# Sheet2.net
KiCad netlist of a schematic drawn in Altium Designer
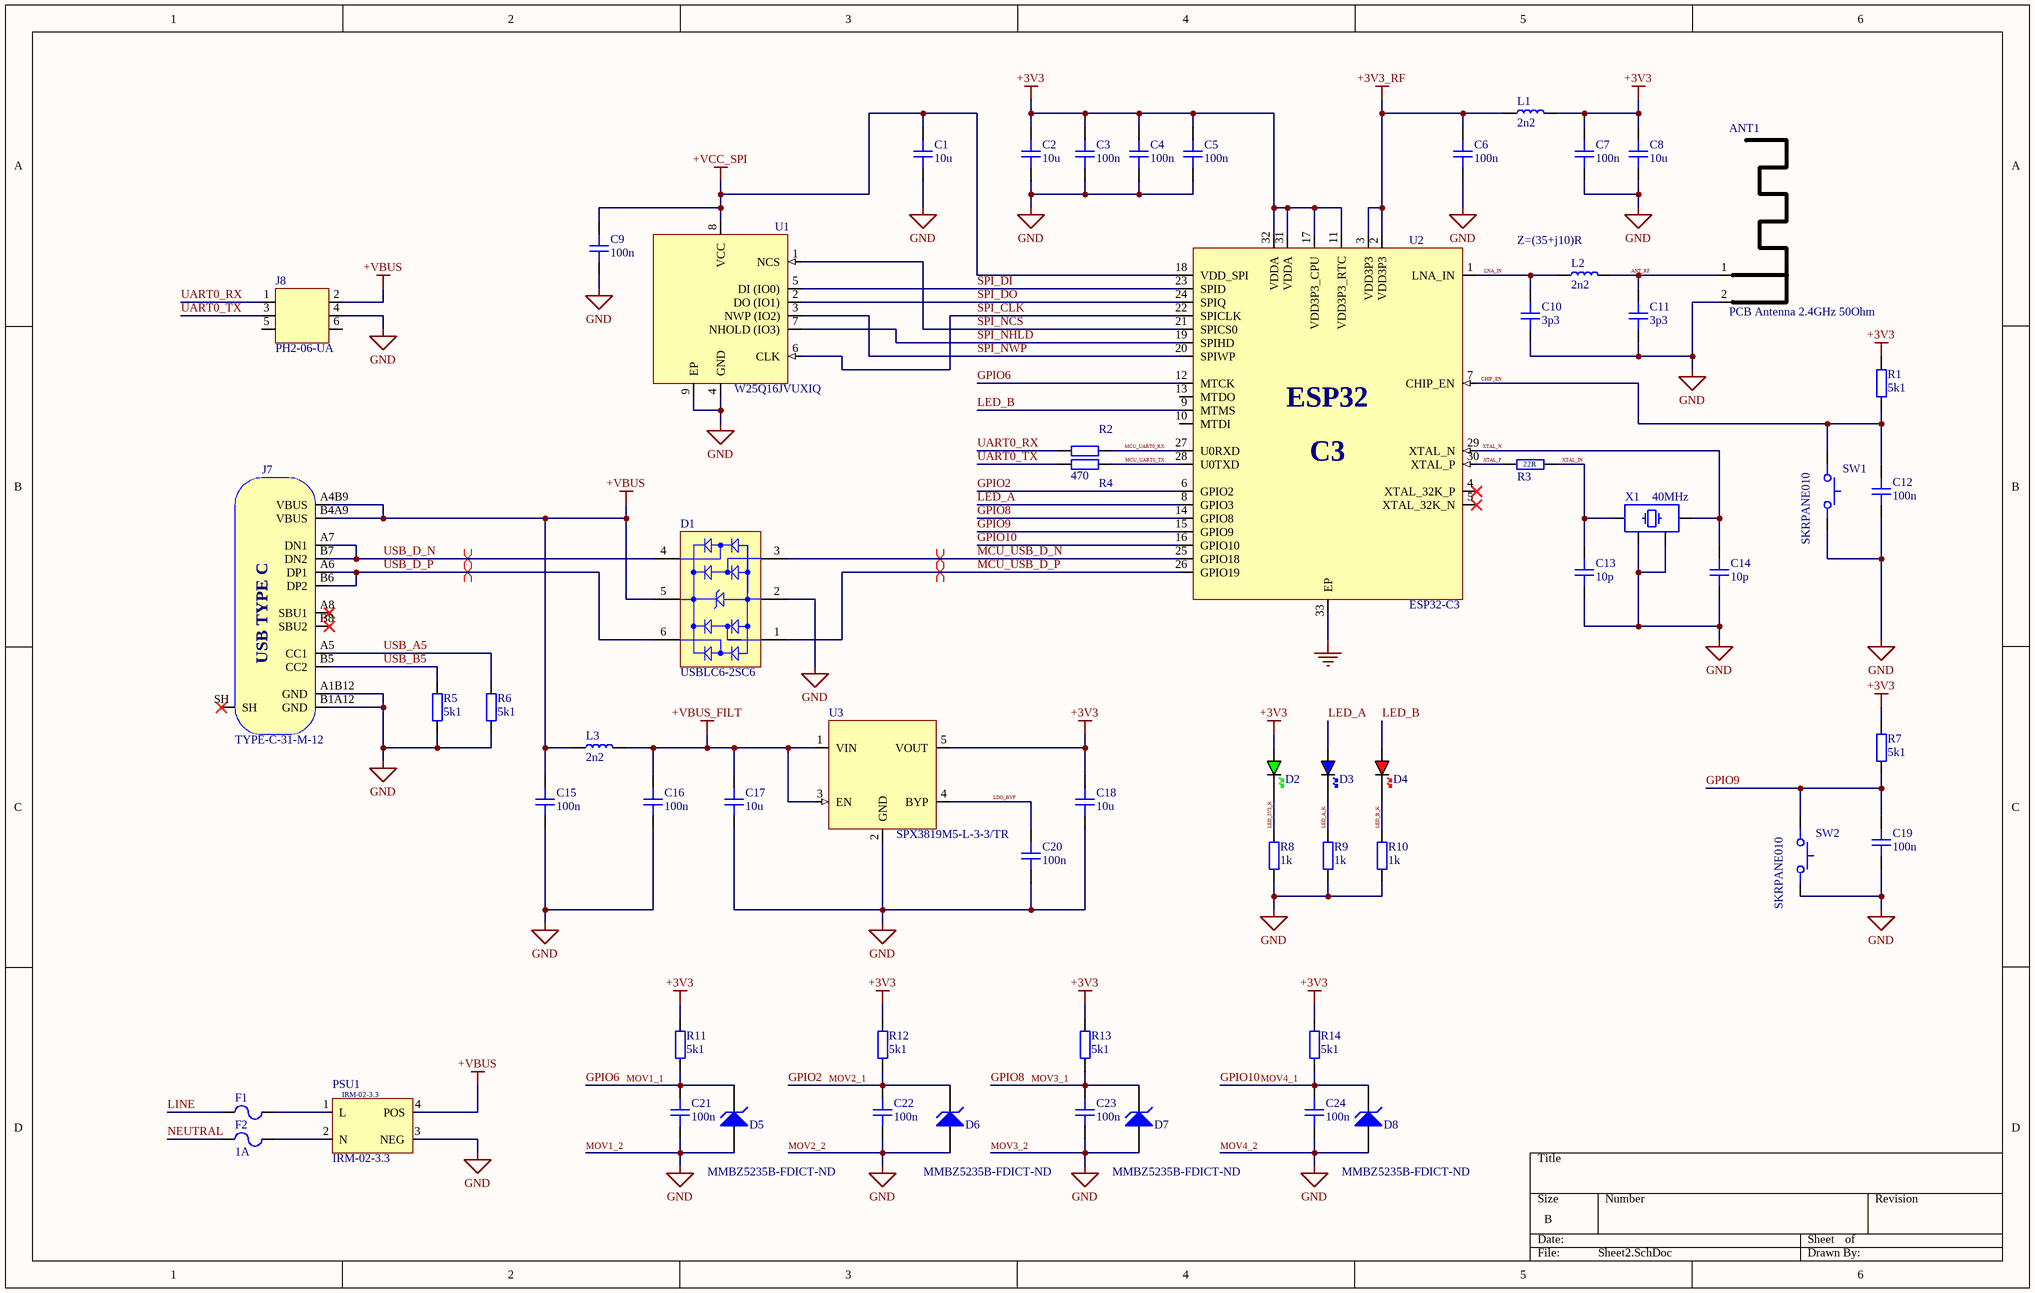
[diagram p0: Sheet2.SchDoc]

(export (version "E")
  (design (tool "Eeschema 10.0.6"))
  (components
    (comp (ref "ANT1")
      (value "PCB Antenna 2.4GHz 50Ohm")
      (footprint "ANT_IFA_USB_2_4GHZ_50R")
      (description "Inverted F 2.4GHz ISM PCB Antenna 50 Ohm")
      (libsource (lib "Schematic-Lib-PhilsLab") (part "ANT_IFA_USB_2_4GHZ_50R"))
    )
    (comp (ref "C1")
      (value "10u")
      (footprint "CAP_0603")
      (description "Capacitor SMD 0603 10V")
      (fields
        (field (name "MANUFACTURER") "Samsung")
        (field (name "MANUFACTURER PART NUMBER") "CL10A106KP8NNNC")
      )
      (libsource (lib "Schematic-Lib-PhilsLab") (part "CAP_0603_10V"))
    )
    (comp (ref "C2")
      (value "10u")
      (footprint "CAP_0603")
      (description "Capacitor SMD 0603 10V")
      (fields
        (field (name "MANUFACTURER") "Samsung")
        (field (name "MANUFACTURER PART NUMBER") "CL10A106KP8NNNC")
      )
      (libsource (lib "Schematic-Lib-PhilsLab") (part "CAP_0603_10V"))
    )
    (comp (ref "C3")
      (value "100n")
      (footprint "CAP_0805")
      (description "Capacitor SMD 0805 50V")
      (libsource (lib "Schematic-Lib-PhilsLab") (part "CAP_0805_50V"))
    )
    (comp (ref "C4")
      (value "100n")
      (footprint "CAP_0805")
      (description "Capacitor SMD 0805 50V")
      (libsource (lib "Schematic-Lib-PhilsLab") (part "CAP_0805_50V"))
    )
    (comp (ref "C5")
      (value "100n")
      (footprint "CAP_0805")
      (description "Capacitor SMD 0805 50V")
      (libsource (lib "Schematic-Lib-PhilsLab") (part "CAP_0805_50V"))
    )
    (comp (ref "C6")
      (value "100n")
      (footprint "CAP_0805")
      (description "Capacitor SMD 0805 50V")
      (libsource (lib "Schematic-Lib-PhilsLab") (part "CAP_0805_50V"))
    )
    (comp (ref "C7")
      (value "100n")
      (footprint "CAP_0805")
      (description "Capacitor SMD 0805 50V")
      (libsource (lib "Schematic-Lib-PhilsLab") (part "CAP_0805_50V"))
    )
    (comp (ref "C8")
      (value "10u")
      (footprint "CAP_0603")
      (description "Capacitor SMD 0603 10V")
      (fields
        (field (name "MANUFACTURER") "Samsung")
        (field (name "MANUFACTURER PART NUMBER") "CL10A106KP8NNNC")
      )
      (libsource (lib "Schematic-Lib-PhilsLab") (part "CAP_0603_10V"))
    )
    (comp (ref "C9")
      (value "100n")
      (footprint "CAP_0805")
      (description "Capacitor SMD 0805 50V")
      (libsource (lib "Schematic-Lib-PhilsLab") (part "CAP_0805_50V"))
    )
    (comp (ref "C10")
      (value "3p3")
      (footprint "CAP_0402")
      (description "Capacitor SMD 0402 50V")
      (fields (field (name "MANUFACTURER") "FH") (field (name "MANUFACTURER PART NUMBER") "0402CG3R3C500NT"))
      (libsource (lib "Schematic-Lib-PhilsLab") (part "CAP_0402_50V"))
    )
    (comp (ref "C11")
      (value "3p3")
      (footprint "CAP_0402")
      (description "Capacitor SMD 0402 50V")
      (fields (field (name "MANUFACTURER") "FH") (field (name "MANUFACTURER PART NUMBER") "0402CG3R3C500NT"))
      (libsource (lib "Schematic-Lib-PhilsLab") (part "CAP_0402_50V"))
    )
    (comp (ref "C12")
      (value "100n")
      (footprint "CAP_0805")
      (description "Capacitor SMD 0805 50V")
      (libsource (lib "Schematic-Lib-PhilsLab") (part "CAP_0805_50V"))
    )
    (comp (ref "C13")
      (value "10p")
      (footprint "CAP_0402")
      (description "Capacitor SMD 0402 50V")
      (fields
        (field (name "MANUFACTURER") "Samsung")
        (field (name "MANUFACTURER PART NUMBER") "CL05C100JB5NNNC")
      )
      (libsource (lib "Schematic-Lib-PhilsLab") (part "CAP_0402_50V"))
    )
    (comp (ref "C14")
      (value "10p")
      (footprint "CAP_0402")
      (description "Capacitor SMD 0402 50V")
      (fields
        (field (name "MANUFACTURER") "Samsung")
        (field (name "MANUFACTURER PART NUMBER") "CL05C100JB5NNNC")
      )
      (libsource (lib "Schematic-Lib-PhilsLab") (part "CAP_0402_50V"))
    )
    (comp (ref "C15")
      (value "100n")
      (footprint "CAP_0805")
      (description "Capacitor SMD 0805 50V")
      (libsource (lib "Schematic-Lib-PhilsLab") (part "CAP_0805_50V"))
    )
    (comp (ref "C16")
      (value "100n")
      (footprint "CAP_0805")
      (description "Capacitor SMD 0805 50V")
      (libsource (lib "Schematic-Lib-PhilsLab") (part "CAP_0805_50V"))
    )
    (comp (ref "C17")
      (value "10u")
      (footprint "CAP_0603")
      (description "Capacitor SMD 0603 10V")
      (fields
        (field (name "MANUFACTURER") "Samsung")
        (field (name "MANUFACTURER PART NUMBER") "CL10A106KP8NNNC")
      )
      (libsource (lib "Schematic-Lib-PhilsLab") (part "CAP_0603_10V"))
    )
    (comp (ref "C18")
      (value "10u")
      (footprint "CAP_0603")
      (description "Capacitor SMD 0603 10V")
      (fields
        (field (name "MANUFACTURER") "Samsung")
        (field (name "MANUFACTURER PART NUMBER") "CL10A106KP8NNNC")
      )
      (libsource (lib "Schematic-Lib-PhilsLab") (part "CAP_0603_10V"))
    )
    (comp (ref "C19")
      (value "100n")
      (footprint "CAP_0805")
      (description "Capacitor SMD 0805 50V")
      (libsource (lib "Schematic-Lib-PhilsLab") (part "CAP_0805_50V"))
    )
    (comp (ref "C20")
      (value "100n")
      (footprint "CAP_0805")
      (description "Capacitor SMD 0805 50V")
      (libsource (lib "Schematic-Lib-PhilsLab") (part "CAP_0805_50V"))
    )
    (comp (ref "C21")
      (value "100n")
      (footprint "CAP_0805")
      (description "Capacitor SMD 0805 50V")
      (libsource (lib "Schematic-Lib-PhilsLab") (part "CAP_0805_50V"))
    )
    (comp (ref "C22")
      (value "100n")
      (footprint "CAP_0805")
      (description "Capacitor SMD 0805 50V")
      (libsource (lib "Schematic-Lib-PhilsLab") (part "CAP_0805_50V"))
    )
    (comp (ref "C23")
      (value "100n")
      (footprint "CAP_0805")
      (description "Capacitor SMD 0805 50V")
      (libsource (lib "Schematic-Lib-PhilsLab") (part "CAP_0805_50V"))
    )
    (comp (ref "C24")
      (value "100n")
      (footprint "CAP_0805")
      (description "Capacitor SMD 0805 50V")
      (libsource (lib "Schematic-Lib-PhilsLab") (part "CAP_0805_50V"))
    )
    (comp (ref "D1")
      (value "USBLC6-2SC6")
      (footprint "STM-SOT23-6L_V")
      (description "Very low capacitance ESD protection, 3.5 pF, -40 to 125 degC, 6-Pin SOT23, RoHS, Tape and Reel")
      (fields (field (name "MANUFACTURER") "STMicroelectronics"))
      (libsource (lib "Altium Content Vault") (part "STM-USB_DVI_HDMIULC6-4SC6X-SOT23-6L"))
    )
    (comp (ref "D2")
      (value "GREEN")
      (footprint "LED_0603_GREEN")
      (description "LED 0603 GREEN SMD")
      (libsource (lib "Schematic-Lib-PhilsLab") (part "LED_0603_GREEN"))
    )
    (comp (ref "D3")
      (value "BLUE")
      (footprint "LED_0603_BLUE")
      (description "LED 0603 BLUE SMD")
      (libsource (lib "Schematic-Lib-PhilsLab") (part "LED_0603_BLUE"))
    )
    (comp (ref "D4")
      (value "RED")
      (footprint "LED_0603_RED")
      (description "LED 0603 RED SMD")
      (libsource (lib "Schematic-Lib-PhilsLab") (part "LED_0603_RED"))
    )
    (comp (ref "D5")
      (value "Diode, Zener, BZX84C18")
      (footprint "SOT23")
      (description "MMBZ5235B Series 350 mW 6.8 V 10 mA Surface Mount Zener Diode - SOT-23")
      (fields
        (field (name "MANUFACTURER") "Diodes")
        (field (name "TOLERANCE") "6%")
        (field (name "SUPPLIER PART NUMBER 2") "MMBZ5235B-FDICT-ND")
      )
      (libsource (lib "Erico_Ignitor") (part "Diode_BZX84C18"))
    )
    (comp (ref "D6")
      (value "Diode, Zener, BZX84C18")
      (footprint "SOT23")
      (description "MMBZ5235B Series 350 mW 6.8 V 10 mA Surface Mount Zener Diode - SOT-23")
      (fields
        (field (name "MANUFACTURER") "Diodes")
        (field (name "TOLERANCE") "6%")
        (field (name "SUPPLIER PART NUMBER 2") "MMBZ5235B-FDICT-ND")
      )
      (libsource (lib "Erico_Ignitor") (part "Diode_BZX84C18"))
    )
    (comp (ref "D7")
      (value "Diode, Zener, BZX84C18")
      (footprint "SOT23")
      (description "MMBZ5235B Series 350 mW 6.8 V 10 mA Surface Mount Zener Diode - SOT-23")
      (fields
        (field (name "MANUFACTURER") "Diodes")
        (field (name "TOLERANCE") "6%")
        (field (name "SUPPLIER PART NUMBER 2") "MMBZ5235B-FDICT-ND")
      )
      (libsource (lib "Erico_Ignitor") (part "Diode_BZX84C18"))
    )
    (comp (ref "D8")
      (value "Diode, Zener, BZX84C18")
      (footprint "SOT23")
      (description "MMBZ5235B Series 350 mW 6.8 V 10 mA Surface Mount Zener Diode - SOT-23")
      (fields
        (field (name "MANUFACTURER") "Diodes")
        (field (name "TOLERANCE") "6%")
        (field (name "SUPPLIER PART NUMBER 2") "MMBZ5235B-FDICT-ND")
      )
      (libsource (lib "Erico_Ignitor") (part "Diode_BZX84C18"))
    )
    (comp (ref "F1")
      (value "1A")
      (footprint "FUSE_6125N")
      (description "0422001.MR")
      (fields (field (name "MANUFACTURER") "Bel"))
      (libsource (lib "Erico_Ignitor") (part "FUSE_4A_SMT"))
    )
    (comp (ref "F2")
      (value "1A")
      (footprint "FUSE_6125N")
      (description "0422001.MR")
      (fields (field (name "MANUFACTURER") "Bel"))
      (libsource (lib "Erico_Ignitor") (part "FUSE_4A_SMT"))
    )
    (comp (ref "J7")
      (value "TYPE-C-31-M-12")
      (footprint "TYPE-C-31-M-12")
      (description "USB Type C Connector Horizontal SMT")
      (fields (field (name "MANUFACTURER") "Koren Hroparts"))
      (libsource (lib "Schematic-Lib-PhilsLab") (part "TYPE-C-31-M-12"))
    )
    (comp (ref "J8")
      (value "PH2-06-UA")
      (footprint "PH2-06-UA")
      (libsource (lib "SchLibrary") (part "PH2-06-UA"))
    )
    (comp (ref "L1")
      (value "2n2")
      (footprint "IND_0402")
      (description "Inductor SMD 0402")
      (fields
        (field (name "MANUFACTURER") "Murata")
        (field (name "MANUFACTURER PART NUMBER") "LQW15AN2N2G80D")
      )
      (libsource (lib "Schematic-Lib-PhilsLab") (part "IND_0402"))
    )
    (comp (ref "L2")
      (value "2n2")
      (footprint "IND_0402")
      (description "Inductor SMD 0402")
      (fields
        (field (name "MANUFACTURER") "Murata")
        (field (name "MANUFACTURER PART NUMBER") "LQW15AN2N2G80D")
      )
      (libsource (lib "Schematic-Lib-PhilsLab") (part "IND_0402"))
    )
    (comp (ref "L3")
      (value "2n2")
      (footprint "IND_0402")
      (description "Inductor SMD 0402")
      (fields
        (field (name "MANUFACTURER") "Murata")
        (field (name "MANUFACTURER PART NUMBER") "LQW15AN2N2G80D")
      )
      (libsource (lib "Schematic-Lib-PhilsLab") (part "IND_0402"))
    )
    (comp (ref "PSU1")
      (value "IRM-02-3.3")
      (footprint "IRM-02-3.3")
      (libsource (lib "SchLibrary") (part "IRM-02-3.3"))
    )
    (comp (ref "R1")
      (value "5k1")
      (footprint "RES_0805")
      (description "Resistor SMD 0805")
      (libsource (lib "Schematic-Lib-PhilsLab") (part "RES_0805"))
    )
    (comp (ref "R2")
      (value "470")
      (footprint "RES_0805")
      (description "Resistor SMD 0805")
      (libsource (lib "Schematic-Lib-PhilsLab") (part "RES_0805"))
    )
    (comp (ref "R3")
      (value "22R")
      (footprint "RES_0402")
      (description "Resistor SMD 0402")
      (fields
        (field (name "MANUFACTURER") "UNI-ROYAL")
        (field (name "MANUFACTURER PART NUMBER") "0402WGF220JTCE")
      )
      (libsource (lib "Schematic-Lib-PhilsLab") (part "RES_0402"))
    )
    (comp (ref "R4")
      (value "470")
      (footprint "RES_0805")
      (description "Resistor SMD 0805")
      (libsource (lib "Schematic-Lib-PhilsLab") (part "RES_0805"))
    )
    (comp (ref "R5")
      (value "5k1")
      (footprint "RES_0805")
      (description "Resistor SMD 0805")
      (libsource (lib "Schematic-Lib-PhilsLab") (part "RES_0805"))
    )
    (comp (ref "R6")
      (value "5k1")
      (footprint "RES_0805")
      (description "Resistor SMD 0805")
      (libsource (lib "Schematic-Lib-PhilsLab") (part "RES_0805"))
    )
    (comp (ref "R7")
      (value "5k1")
      (footprint "RES_0805")
      (description "Resistor SMD 0805")
      (libsource (lib "Schematic-Lib-PhilsLab") (part "RES_0805"))
    )
    (comp (ref "R8")
      (value "1k")
      (footprint "RES_0805")
      (description "Resistor SMD 0805")
      (libsource (lib "Schematic-Lib-PhilsLab") (part "RES_0805"))
    )
    (comp (ref "R9")
      (value "1k")
      (footprint "RES_0805")
      (description "Resistor SMD 0805")
      (libsource (lib "Schematic-Lib-PhilsLab") (part "RES_0805"))
    )
    (comp (ref "R10")
      (value "1k")
      (footprint "RES_0805")
      (description "Resistor SMD 0805")
      (libsource (lib "Schematic-Lib-PhilsLab") (part "RES_0805"))
    )
    (comp (ref "R11")
      (value "5k1")
      (footprint "RES_0805")
      (description "Resistor SMD 0805")
      (libsource (lib "Schematic-Lib-PhilsLab") (part "RES_0805"))
    )
    (comp (ref "R12")
      (value "5k1")
      (footprint "RES_0805")
      (description "Resistor SMD 0805")
      (libsource (lib "Schematic-Lib-PhilsLab") (part "RES_0805"))
    )
    (comp (ref "R13")
      (value "5k1")
      (footprint "RES_0805")
      (description "Resistor SMD 0805")
      (libsource (lib "Schematic-Lib-PhilsLab") (part "RES_0805"))
    )
    (comp (ref "R14")
      (value "5k1")
      (footprint "RES_0805")
      (description "Resistor SMD 0805")
      (libsource (lib "Schematic-Lib-PhilsLab") (part "RES_0805"))
    )
    (comp (ref "SW1")
      (value "SKRPANE010")
      (footprint "SKRPANE010")
      (description "Tactile Switch SMD SPST")
      (fields (field (name "MANUFACTURER") "Alps Alpine"))
      (libsource (lib "Schematic-Lib-PhilsLab") (part "SKRPANE010"))
    )
    (comp (ref "SW2")
      (value "SKRPANE010")
      (footprint "SKRPANE010")
      (description "Tactile Switch SMD SPST")
      (fields (field (name "MANUFACTURER") "Alps Alpine"))
      (libsource (lib "Schematic-Lib-PhilsLab") (part "SKRPANE010"))
    )
    (comp (ref "U1")
      (value "W25Q16JVUXIQ")
      (footprint "USON-8-2X3MM")
      (description "16M-BIT SERIAL FLASH MEMORY WITH\r\nDUAL/QUAD SPI USON-8")
      (fields (field (name "MANUFACTURER") "Winbond"))
      (libsource (lib "Schematic-Lib-PhilsLab") (part "W25Q16JVUXIQ"))
    )
    (comp (ref "U2")
      (value "ESP32-C3")
      (footprint "QFN32-5x5")
      (fields (field (name "MANUFACTURER") "Espressif"))
      (libsource (lib "Schematic-Lib-PhilsLab") (part "ESP32-C3"))
    )
    (comp (ref "U3")
      (value "SPX3819M5-L-3-3/TR")
      (footprint "SOT-23-5")
      (description "500mA +3.3V Low-Noise LDO Voltage Regulator")
      (fields (field (name "MANUFACTURER") "MaxLinear"))
      (libsource (lib "Schematic-Lib-PhilsLab") (part "SPX3819M5-L-3-3/TR"))
    )
    (comp (ref "X1")
      (value "40MHz")
      (footprint "XTAL_2520")
      (description "Crystal SMD 2520")
      (fields (field (name "MANUFACTURER") "Seiko Epson"))
      (libsource (lib "Schematic-Lib-PhilsLab") (part "XTAL_2520"))
    )
  )
  (nets
    (net (code "1") (name "+3V3") (class "Default")
      (node (ref "C18") (pin "2") (pinfunction "2_2") (pintype "passive"))
      (node (ref "C2") (pin "2") (pinfunction "2_2") (pintype "passive"))
      (node (ref "C3") (pin "2") (pinfunction "2_2") (pintype "passive"))
      (node (ref "C4") (pin "2") (pinfunction "2_2") (pintype "passive"))
      (node (ref "C5") (pin "2") (pinfunction "2_2") (pintype "passive"))
      (node (ref "C7") (pin "2") (pinfunction "2_2") (pintype "passive"))
      (node (ref "C8") (pin "2") (pinfunction "2_2") (pintype "passive"))
      (node (ref "D2") (pin "A") (pinfunction "A_A") (pintype "passive"))
      (node (ref "L1") (pin "1") (pinfunction "1_1") (pintype "passive"))
      (node (ref "R1") (pin "2") (pinfunction "2_2") (pintype "passive"))
      (node (ref "R11") (pin "2") (pinfunction "2_2") (pintype "passive"))
      (node (ref "R12") (pin "2") (pinfunction "2_2") (pintype "passive"))
      (node (ref "R13") (pin "2") (pinfunction "2_2") (pintype "passive"))
      (node (ref "R14") (pin "2") (pinfunction "2_2") (pintype "passive"))
      (node (ref "R7") (pin "2") (pinfunction "2_2") (pintype "passive"))
      (node (ref "U2") (pin "11") (pinfunction "VDD3P3_RTC_11") (pintype "power_in"))
      (node (ref "U2") (pin "17") (pinfunction "VDD3P3_CPU_17") (pintype "power_in"))
      (node (ref "U2") (pin "31") (pinfunction "VDDA_31") (pintype "power_in"))
      (node (ref "U2") (pin "32") (pinfunction "VDDA_32") (pintype "power_in"))
      (node (ref "U3") (pin "5") (pinfunction "VOUT_5") (pintype "power_in"))
    )
    (net (code "2") (name "+3V3_RF") (class "Default")
      (node (ref "C6") (pin "2") (pinfunction "2_2") (pintype "passive"))
      (node (ref "L1") (pin "2") (pinfunction "2_2") (pintype "passive"))
      (node (ref "U2") (pin "2") (pinfunction "VDD3P3_2") (pintype "power_in"))
      (node (ref "U2") (pin "3") (pinfunction "VDD3P3_3") (pintype "power_in"))
    )
    (net (code "3") (name "+VBUS") (class "Default")
      (node (ref "C15") (pin "2") (pinfunction "2_2") (pintype "passive"))
      (node (ref "D1") (pin "5") (pinfunction "VBUS_5") (pintype "passive"))
      (node (ref "J7") (pin "A4B9") (pinfunction "VBUS_A4B9") (pintype "power_in"))
      (node (ref "J7") (pin "B4A9") (pinfunction "VBUS_B4A9") (pintype "power_in"))
      (node (ref "J8") (pin "2") (pinfunction "2_2") (pintype "passive"))
      (node (ref "L3") (pin "2") (pinfunction "2_2") (pintype "passive"))
      (node (ref "PSU1") (pin "4") (pinfunction "POS_4") (pintype "passive"))
    )
    (net (code "4") (name "+VBUS_FILT") (class "Default")
      (node (ref "C16") (pin "2") (pinfunction "2_2") (pintype "passive"))
      (node (ref "C17") (pin "2") (pinfunction "2_2") (pintype "passive"))
      (node (ref "L3") (pin "1") (pinfunction "1_1") (pintype "passive"))
      (node (ref "U3") (pin "1") (pinfunction "VIN_1") (pintype "power_in"))
      (node (ref "U3") (pin "3") (pinfunction "EN_3") (pintype "input"))
    )
    (net (code "5") (name "+VCC_SPI") (class "Default")
      (node (ref "C1") (pin "2") (pinfunction "2_2") (pintype "passive"))
      (node (ref "C9") (pin "2") (pinfunction "2_2") (pintype "passive"))
      (node (ref "U1") (pin "8") (pinfunction "VCC_8") (pintype "power_in"))
      (node (ref "U2") (pin "18") (pinfunction "VDD_SPI_18") (pintype "power_in"))
    )
    (net (code "6") (name "/ANT_RF") (class "Default")
      (node (ref "ANT1") (pin "1") (pinfunction "RF_1") (pintype "passive"))
      (node (ref "C11") (pin "2") (pinfunction "2_2") (pintype "passive"))
      (node (ref "L2") (pin "1") (pinfunction "1_1") (pintype "passive"))
    )
    (net (code "7") (name "/CHIP_EN") (class "Default")
      (node (ref "C12") (pin "2") (pinfunction "2_2") (pintype "passive"))
      (node (ref "R1") (pin "1") (pinfunction "1_1") (pintype "passive"))
      (node (ref "SW1") (pin "34") (pintype "passive"))
      (node (ref "U2") (pin "7") (pinfunction "CHIP_EN_7") (pintype "input"))
    )
    (net (code "8") (name "/GPIO2") (class "Default")
      (node (ref "C22") (pin "2") (pinfunction "2_2") (pintype "passive"))
      (node (ref "D6") (pin "3") (pinfunction "K_3") (pintype "passive"))
      (node (ref "R12") (pin "1") (pinfunction "1_1") (pintype "passive"))
      (node (ref "U2") (pin "6") (pinfunction "GPIO2_6") (pintype "bidirectional"))
    )
    (net (code "9") (name "/GPIO6") (class "Default")
      (node (ref "C21") (pin "2") (pinfunction "2_2") (pintype "passive"))
      (node (ref "D5") (pin "3") (pinfunction "K_3") (pintype "passive"))
      (node (ref "R11") (pin "1") (pinfunction "1_1") (pintype "passive"))
      (node (ref "U2") (pin "12") (pinfunction "MTCK_12") (pintype "bidirectional"))
    )
    (net (code "10") (name "/GPIO8") (class "Default")
      (node (ref "C23") (pin "2") (pinfunction "2_2") (pintype "passive"))
      (node (ref "D7") (pin "3") (pinfunction "K_3") (pintype "passive"))
      (node (ref "R13") (pin "1") (pinfunction "1_1") (pintype "passive"))
      (node (ref "U2") (pin "14") (pinfunction "GPIO8_14") (pintype "bidirectional"))
    )
    (net (code "11") (name "/GPIO9") (class "Default")
      (node (ref "C19") (pin "2") (pinfunction "2_2") (pintype "passive"))
      (node (ref "R7") (pin "1") (pinfunction "1_1") (pintype "passive"))
      (node (ref "SW2") (pin "34") (pintype "passive"))
      (node (ref "U2") (pin "15") (pinfunction "GPIO9_15") (pintype "bidirectional"))
    )
    (net (code "12") (name "/GPIO10") (class "Default")
      (node (ref "C24") (pin "2") (pinfunction "2_2") (pintype "passive"))
      (node (ref "D8") (pin "3") (pinfunction "K_3") (pintype "passive"))
      (node (ref "R14") (pin "1") (pinfunction "1_1") (pintype "passive"))
      (node (ref "U2") (pin "16") (pinfunction "GPIO10_16") (pintype "bidirectional"))
    )
    (net (code "13") (name "/LDO_BYP") (class "Default")
      (node (ref "C20") (pin "2") (pinfunction "2_2") (pintype "passive"))
      (node (ref "U3") (pin "4") (pinfunction "BYP_4") (pintype "passive"))
    )
    (net (code "14") (name "/LED_3V3_K") (class "Default")
      (node (ref "D2") (pin "K") (pinfunction "K_K") (pintype "passive"))
      (node (ref "R8") (pin "2") (pinfunction "2_2") (pintype "passive"))
    )
    (net (code "15") (name "/LED_A") (class "Default")
      (node (ref "D3") (pin "A") (pinfunction "A_A") (pintype "passive"))
      (node (ref "U2") (pin "8") (pinfunction "GPIO3_8") (pintype "bidirectional"))
    )
    (net (code "16") (name "/LED_A_K") (class "Default")
      (node (ref "D3") (pin "K") (pinfunction "K_K") (pintype "passive"))
      (node (ref "R9") (pin "2") (pinfunction "2_2") (pintype "passive"))
    )
    (net (code "17") (name "/LED_B") (class "Default")
      (node (ref "D4") (pin "A") (pinfunction "A_A") (pintype "passive"))
      (node (ref "U2") (pin "9") (pinfunction "MTMS_9") (pintype "bidirectional"))
    )
    (net (code "18") (name "/LED_B_K") (class "Default")
      (node (ref "D4") (pin "K") (pinfunction "K_K") (pintype "passive"))
      (node (ref "R10") (pin "2") (pinfunction "2_2") (pintype "passive"))
    )
    (net (code "19") (name "/LINE") (class "Default")
      (node (ref "F1") (pin "1") (pinfunction "1_1") (pintype "passive"))
    )
    (net (code "20") (name "/LNA_IN") (class "Default")
      (node (ref "C10") (pin "2") (pinfunction "2_2") (pintype "passive"))
      (node (ref "L2") (pin "2") (pinfunction "2_2") (pintype "passive"))
      (node (ref "U2") (pin "1") (pinfunction "LNA_IN_1") (pintype "bidirectional"))
    )
    (net (code "21") (name "/MCU_UART0_RX") (class "Default")
      (node (ref "R2") (pin "1") (pinfunction "1_1") (pintype "passive"))
      (node (ref "U2") (pin "27") (pinfunction "U0RXD_27") (pintype "bidirectional"))
    )
    (net (code "22") (name "/MCU_UART0_TX") (class "Default")
      (node (ref "R4") (pin "1") (pinfunction "1_1") (pintype "passive"))
      (node (ref "U2") (pin "28") (pinfunction "U0TXD_28") (pintype "bidirectional"))
    )
    (net (code "23") (name "/MCU_USB_D_N") (class "Default")
      (node (ref "D1") (pin "3") (pinfunction "I/O_2_3") (pintype "passive"))
      (node (ref "U2") (pin "25") (pinfunction "GPIO18_25") (pintype "bidirectional"))
    )
    (net (code "24") (name "/MCU_USB_D_P") (class "Default")
      (node (ref "D1") (pin "1") (pinfunction "I/O_1_1") (pintype "passive"))
      (node (ref "U2") (pin "26") (pinfunction "GPIO19_26") (pintype "bidirectional"))
    )
    (net (code "25") (name "/NEUTRAL") (class "Default")
      (node (ref "F2") (pin "1") (pinfunction "1_1") (pintype "passive"))
    )
    (net (code "26") (name "/SPI_CLK") (class "Default")
      (node (ref "U1") (pin "6") (pinfunction "CLK_6") (pintype "input"))
      (node (ref "U2") (pin "22") (pinfunction "SPICLK_22") (pintype "bidirectional"))
    )
    (net (code "27") (name "/SPI_DI") (class "Default")
      (node (ref "U1") (pin "5") (pinfunction "DI_(IO0)_5") (pintype "bidirectional"))
      (node (ref "U2") (pin "23") (pinfunction "SPID_23") (pintype "bidirectional"))
    )
    (net (code "28") (name "/SPI_DO") (class "Default")
      (node (ref "U1") (pin "2") (pinfunction "DO_(IO1)_2") (pintype "bidirectional"))
      (node (ref "U2") (pin "24") (pinfunction "SPIQ_24") (pintype "bidirectional"))
    )
    (net (code "29") (name "/SPI_NCS") (class "Default")
      (node (ref "U1") (pin "1") (pinfunction "NCS_1") (pintype "input"))
      (node (ref "U2") (pin "21") (pinfunction "SPICS0_21") (pintype "bidirectional"))
    )
    (net (code "30") (name "/SPI_NHLD") (class "Default")
      (node (ref "U1") (pin "7") (pinfunction "NHOLD_(IO3)_7") (pintype "bidirectional"))
      (node (ref "U2") (pin "19") (pinfunction "SPIHD_19") (pintype "bidirectional"))
    )
    (net (code "31") (name "/SPI_NWP") (class "Default")
      (node (ref "U1") (pin "3") (pinfunction "NWP_(IO2)_3") (pintype "bidirectional"))
      (node (ref "U2") (pin "20") (pinfunction "SPIWP_20") (pintype "bidirectional"))
    )
    (net (code "32") (name "/UART0_RX") (class "Default")
      (node (ref "J8") (pin "1") (pinfunction "1_1") (pintype "passive"))
      (node (ref "R2") (pin "2") (pinfunction "2_2") (pintype "passive"))
    )
    (net (code "33") (name "/UART0_TX") (class "Default")
      (node (ref "J8") (pin "3") (pinfunction "3_3") (pintype "passive"))
      (node (ref "R4") (pin "2") (pinfunction "2_2") (pintype "passive"))
    )
    (net (code "34") (name "/USB_A5") (class "Default")
      (node (ref "J7") (pin "A5") (pinfunction "CC1_A5") (pintype "passive"))
      (node (ref "R6") (pin "2") (pinfunction "2_2") (pintype "passive"))
    )
    (net (code "35") (name "/USB_B5") (class "Default")
      (node (ref "J7") (pin "B5") (pinfunction "CC2_B5") (pintype "tri_state"))
      (node (ref "R5") (pin "2") (pinfunction "2_2") (pintype "passive"))
    )
    (net (code "36") (name "/USB_D_N") (class "Default")
      (node (ref "D1") (pin "4") (pinfunction "I/O_3_4") (pintype "passive"))
      (node (ref "J7") (pin "A7") (pinfunction "DN1_A7") (pintype "bidirectional"))
      (node (ref "J7") (pin "B7") (pinfunction "DN2_B7") (pintype "bidirectional"))
    )
    (net (code "37") (name "/USB_D_P") (class "Default")
      (node (ref "D1") (pin "6") (pinfunction "I/O_4_6") (pintype "passive"))
      (node (ref "J7") (pin "A6") (pinfunction "DP1_A6") (pintype "bidirectional"))
      (node (ref "J7") (pin "B6") (pinfunction "DP2_B6") (pintype "bidirectional"))
    )
    (net (code "38") (name "/XTAL_IN") (class "Default")
      (node (ref "C13") (pin "2") (pinfunction "2_2") (pintype "passive"))
      (node (ref "R3") (pin "2") (pinfunction "2_2") (pintype "passive"))
      (node (ref "X1") (pin "3") (pinfunction "3_3") (pintype "passive"))
    )
    (net (code "39") (name "/XTAL_N") (class "Default")
      (node (ref "C14") (pin "2") (pinfunction "2_2") (pintype "passive"))
      (node (ref "U2") (pin "29") (pinfunction "XTAL_N_29") (pintype "input"))
      (node (ref "X1") (pin "1") (pinfunction "1_1") (pintype "passive"))
    )
    (net (code "40") (name "/XTAL_P") (class "Default")
      (node (ref "R3") (pin "1") (pinfunction "1_1") (pintype "passive"))
      (node (ref "U2") (pin "30") (pinfunction "XTAL_P_30") (pintype "input"))
    )
    (net (code "41") (name "GND") (class "Default")
      (node (ref "ANT1") (pin "2") (pinfunction "GND_2") (pintype "passive"))
      (node (ref "C1") (pin "1") (pinfunction "1_1") (pintype "passive"))
      (node (ref "C10") (pin "1") (pinfunction "1_1") (pintype "passive"))
      (node (ref "C11") (pin "1") (pinfunction "1_1") (pintype "passive"))
      (node (ref "C12") (pin "1") (pinfunction "1_1") (pintype "passive"))
      (node (ref "C13") (pin "1") (pinfunction "1_1") (pintype "passive"))
      (node (ref "C14") (pin "1") (pinfunction "1_1") (pintype "passive"))
      (node (ref "C15") (pin "1") (pinfunction "1_1") (pintype "passive"))
      (node (ref "C16") (pin "1") (pinfunction "1_1") (pintype "passive"))
      (node (ref "C17") (pin "1") (pinfunction "1_1") (pintype "passive"))
      (node (ref "C18") (pin "1") (pinfunction "1_1") (pintype "passive"))
      (node (ref "C19") (pin "1") (pinfunction "1_1") (pintype "passive"))
      (node (ref "C2") (pin "1") (pinfunction "1_1") (pintype "passive"))
      (node (ref "C20") (pin "1") (pinfunction "1_1") (pintype "passive"))
      (node (ref "C21") (pin "1") (pinfunction "1_1") (pintype "passive"))
      (node (ref "C22") (pin "1") (pinfunction "1_1") (pintype "passive"))
      (node (ref "C23") (pin "1") (pinfunction "1_1") (pintype "passive"))
      (node (ref "C24") (pin "1") (pinfunction "1_1") (pintype "passive"))
      (node (ref "C3") (pin "1") (pinfunction "1_1") (pintype "passive"))
      (node (ref "C4") (pin "1") (pinfunction "1_1") (pintype "passive"))
      (node (ref "C5") (pin "1") (pinfunction "1_1") (pintype "passive"))
      (node (ref "C6") (pin "1") (pinfunction "1_1") (pintype "passive"))
      (node (ref "C7") (pin "1") (pinfunction "1_1") (pintype "passive"))
      (node (ref "C8") (pin "1") (pinfunction "1_1") (pintype "passive"))
      (node (ref "C9") (pin "1") (pinfunction "1_1") (pintype "passive"))
      (node (ref "D1") (pin "2") (pinfunction "GND_2") (pintype "passive"))
      (node (ref "D5") (pin "1") (pinfunction "A_1") (pintype "passive"))
      (node (ref "D6") (pin "1") (pinfunction "A_1") (pintype "passive"))
      (node (ref "D7") (pin "1") (pinfunction "A_1") (pintype "passive"))
      (node (ref "D8") (pin "1") (pinfunction "A_1") (pintype "passive"))
      (node (ref "J7") (pin "A1B12") (pinfunction "GND_A1B12") (pintype "power_in"))
      (node (ref "J7") (pin "B1A12") (pinfunction "GND_B1A12") (pintype "power_in"))
      (node (ref "J8") (pin "4") (pinfunction "4_4") (pintype "passive"))
      (node (ref "PSU1") (pin "3") (pinfunction "NEG_3") (pintype "passive"))
      (node (ref "R10") (pin "1") (pinfunction "1_1") (pintype "passive"))
      (node (ref "R5") (pin "1") (pinfunction "1_1") (pintype "passive"))
      (node (ref "R6") (pin "1") (pinfunction "1_1") (pintype "passive"))
      (node (ref "R8") (pin "1") (pinfunction "1_1") (pintype "passive"))
      (node (ref "R9") (pin "1") (pinfunction "1_1") (pintype "passive"))
      (node (ref "SW1") (pin "12") (pintype "passive"))
      (node (ref "SW2") (pin "12") (pintype "passive"))
      (node (ref "U1") (pin "4") (pinfunction "GND_4") (pintype "power_in"))
      (node (ref "U1") (pin "9") (pinfunction "EP_9") (pintype "power_in"))
      (node (ref "U2") (pin "33") (pinfunction "EP_33") (pintype "power_in"))
      (node (ref "U3") (pin "2") (pinfunction "GND_2") (pintype "power_in"))
      (node (ref "X1") (pin "2") (pinfunction "2_2") (pintype "passive"))
      (node (ref "X1") (pin "4") (pinfunction "4_4") (pintype "passive"))
    )
    (net (code "42") (name "Net-(PSU1-L)") (class "Default")
      (node (ref "F1") (pin "2") (pinfunction "2_2") (pintype "passive"))
      (node (ref "PSU1") (pin "1") (pinfunction "L_1") (pintype "passive"))
    )
    (net (code "43") (name "Net-(PSU1-N)") (class "Default")
      (node (ref "F2") (pin "2") (pinfunction "2_2") (pintype "passive"))
      (node (ref "PSU1") (pin "2") (pinfunction "N_2") (pintype "passive"))
    )
    (net (code "44") (name "unconnected-(J7-PadSH)") (class "Default")
      (node (ref "J7") (pin "SH") (pinfunction "SH_SH") (pintype "power_in+no_connect"))
    )
    (net (code "45") (name "unconnected-(J7-SBU1-PadA8)") (class "Default")
      (node (ref "J7") (pin "A8") (pinfunction "SBU1_A8") (pintype "bidirectional+no_connect"))
    )
    (net (code "46") (name "unconnected-(J7-SBU2-PadB8)") (class "Default")
      (node (ref "J7") (pin "B8") (pinfunction "SBU2_B8") (pintype "bidirectional+no_connect"))
    )
    (net (code "47") (name "unconnected-(J8-Pad5)") (class "Default")
      (node (ref "J8") (pin "5") (pinfunction "5_5") (pintype "passive"))
    )
    (net (code "48") (name "unconnected-(J8-Pad6)") (class "Default")
      (node (ref "J8") (pin "6") (pinfunction "6_6") (pintype "passive"))
    )
    (net (code "49") (name "unconnected-(U2-MTDI-Pad10)") (class "Default")
      (node (ref "U2") (pin "10") (pinfunction "MTDI_10") (pintype "bidirectional"))
    )
    (net (code "50") (name "unconnected-(U2-MTDO-Pad13)") (class "Default")
      (node (ref "U2") (pin "13") (pinfunction "MTDO_13") (pintype "bidirectional"))
    )
    (net (code "51") (name "unconnected-(U2-XTAL_32K_N-Pad5)") (class "Default")
      (node (ref "U2") (pin "5") (pinfunction "XTAL_32K_N_5") (pintype "bidirectional+no_connect"))
    )
    (net (code "52") (name "unconnected-(U2-XTAL_32K_P-Pad4)") (class "Default")
      (node (ref "U2") (pin "4") (pinfunction "XTAL_32K_P_4") (pintype "bidirectional+no_connect"))
    )
  )
)
